# power.net
KiCad netlist of a schematic drawn in EAGLE
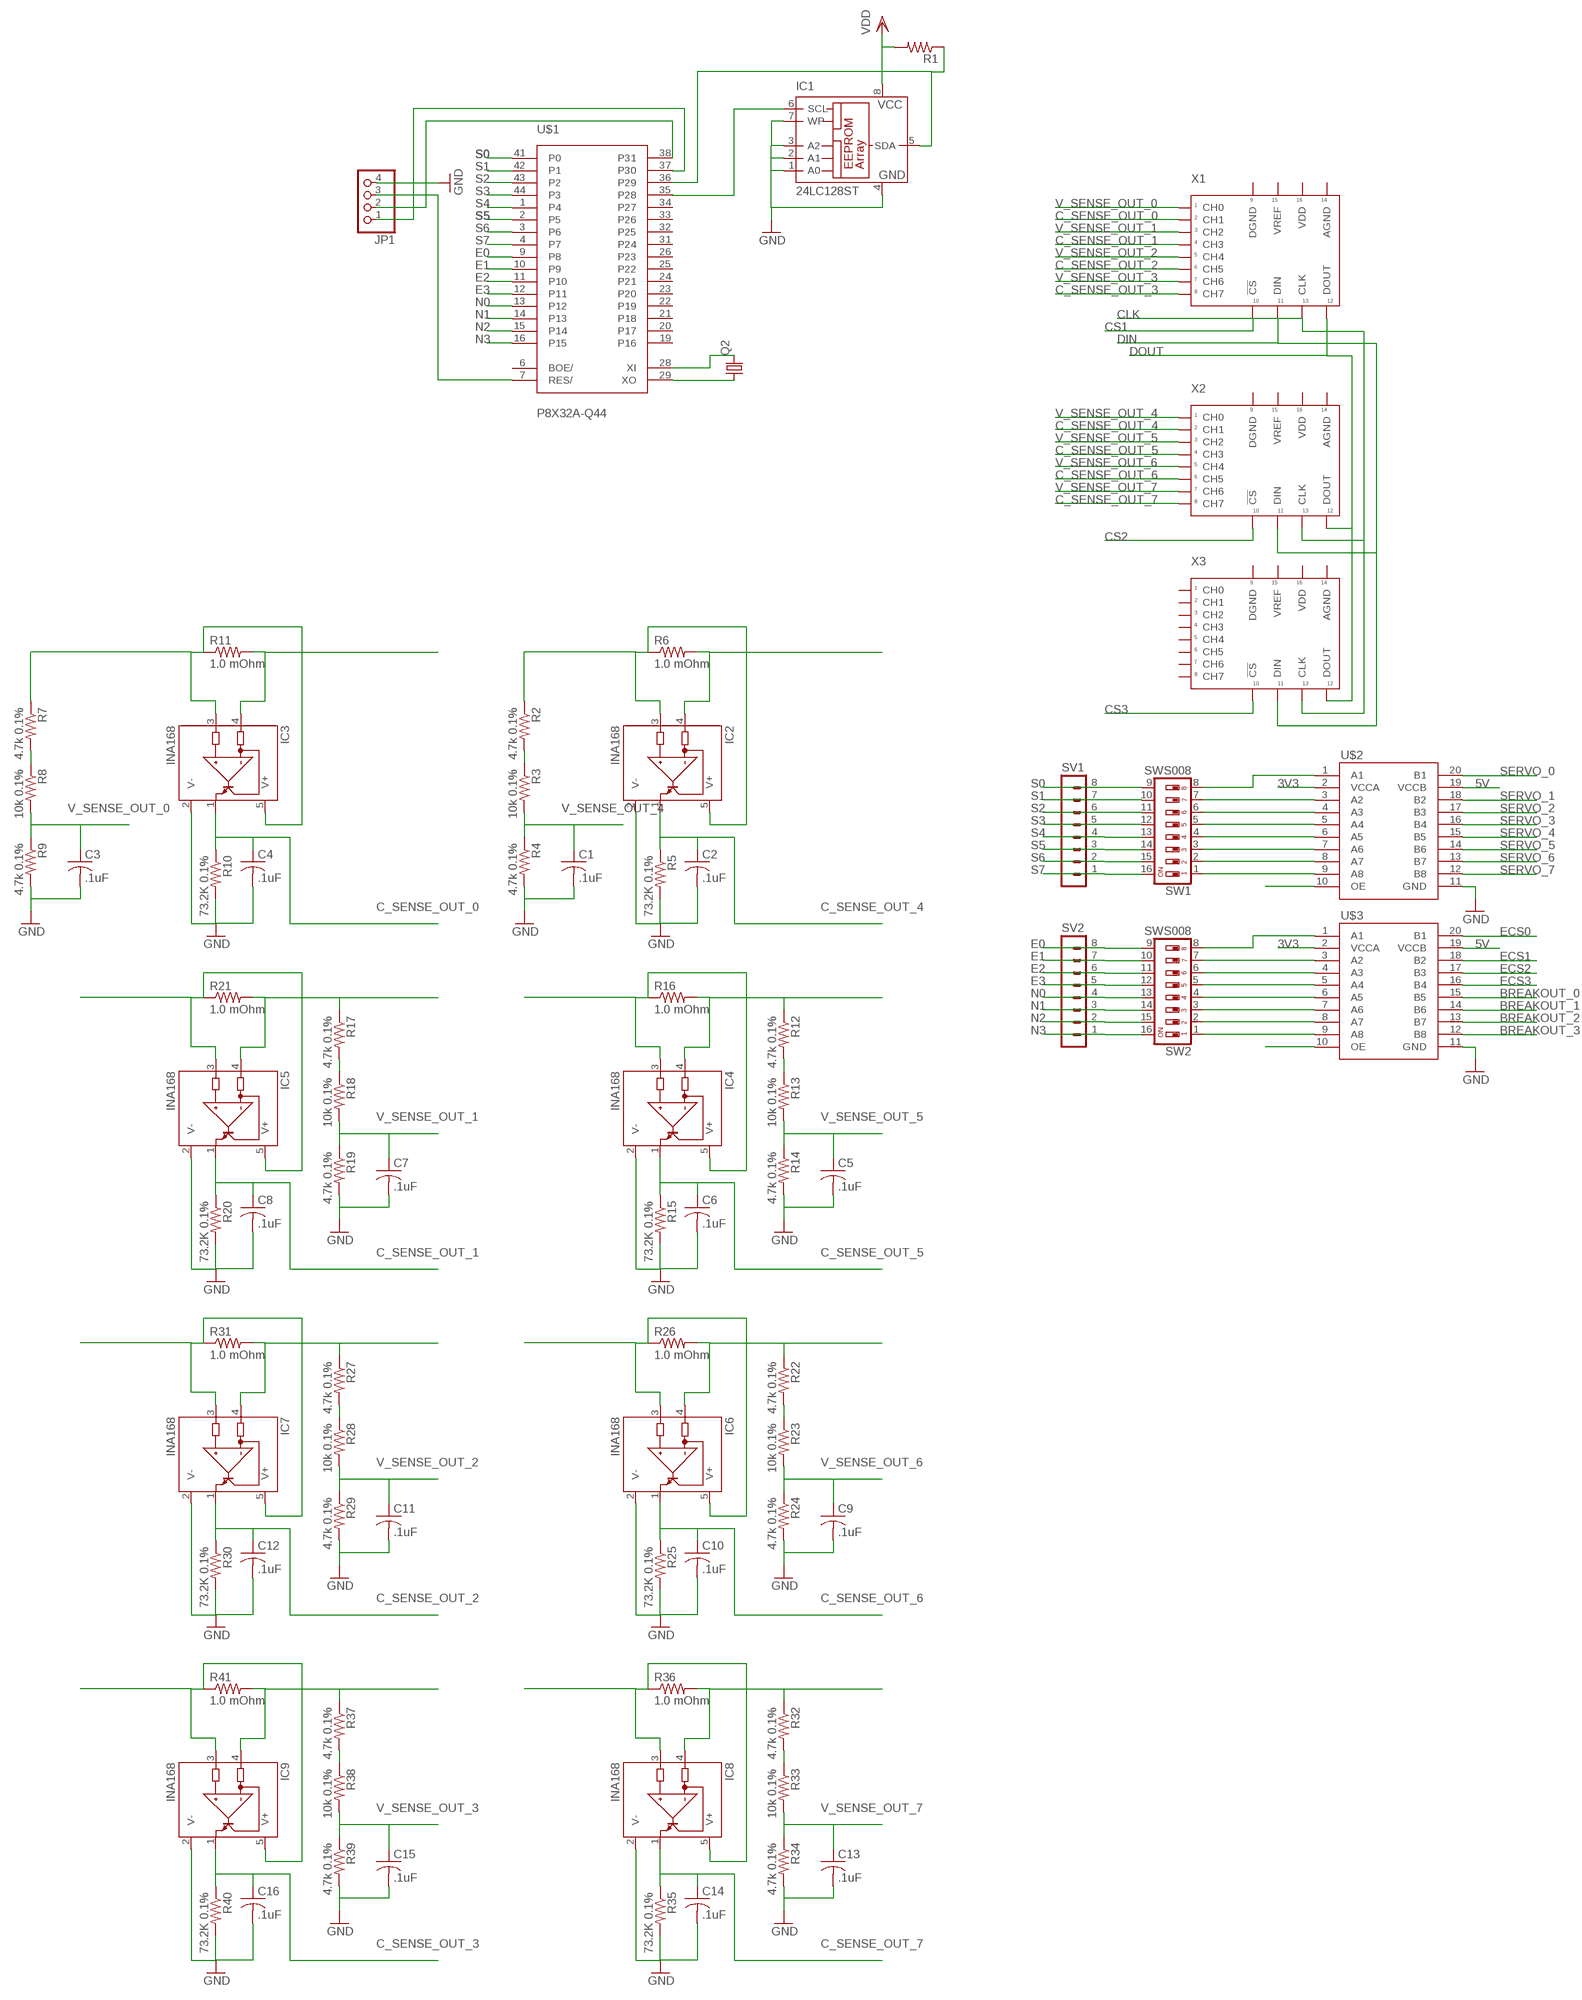
[diagram p0: schematic, sheet 1]

(export (version "E")
  (design (tool "Eeschema 10.0.6"))
  (components
    (comp (ref "C1")
      (value ".1uF")
      (footprint "eagle-import:C0805")
      (libsource (lib "eagle-import") (part "C-USC0805"))
    )
    (comp (ref "C2")
      (value ".1uF")
      (footprint "eagle-import:C0805")
      (libsource (lib "eagle-import") (part "C-USC0805"))
    )
    (comp (ref "C3")
      (value ".1uF")
      (footprint "eagle-import:C0805")
      (libsource (lib "eagle-import") (part "C-USC0805"))
    )
    (comp (ref "C4")
      (value ".1uF")
      (footprint "eagle-import:C0805")
      (libsource (lib "eagle-import") (part "C-USC0805"))
    )
    (comp (ref "C5")
      (value ".1uF")
      (footprint "eagle-import:C0805")
      (libsource (lib "eagle-import") (part "C-USC0805"))
    )
    (comp (ref "C6")
      (value ".1uF")
      (footprint "eagle-import:C0805")
      (libsource (lib "eagle-import") (part "C-USC0805"))
    )
    (comp (ref "C7")
      (value ".1uF")
      (footprint "eagle-import:C0805")
      (libsource (lib "eagle-import") (part "C-USC0805"))
    )
    (comp (ref "C8")
      (value ".1uF")
      (footprint "eagle-import:C0805")
      (libsource (lib "eagle-import") (part "C-USC0805"))
    )
    (comp (ref "C9")
      (value ".1uF")
      (footprint "eagle-import:C0805")
      (libsource (lib "eagle-import") (part "C-USC0805"))
    )
    (comp (ref "C10")
      (value ".1uF")
      (footprint "eagle-import:C0805")
      (libsource (lib "eagle-import") (part "C-USC0805"))
    )
    (comp (ref "C11")
      (value ".1uF")
      (footprint "eagle-import:C0805")
      (libsource (lib "eagle-import") (part "C-USC0805"))
    )
    (comp (ref "C12")
      (value ".1uF")
      (footprint "eagle-import:C0805")
      (libsource (lib "eagle-import") (part "C-USC0805"))
    )
    (comp (ref "C13")
      (value ".1uF")
      (footprint "eagle-import:C0805")
      (libsource (lib "eagle-import") (part "C-USC0805"))
    )
    (comp (ref "C14")
      (value ".1uF")
      (footprint "eagle-import:C0805")
      (libsource (lib "eagle-import") (part "C-USC0805"))
    )
    (comp (ref "C15")
      (value ".1uF")
      (footprint "eagle-import:C0805")
      (libsource (lib "eagle-import") (part "C-USC0805"))
    )
    (comp (ref "C16")
      (value ".1uF")
      (footprint "eagle-import:C0805")
      (libsource (lib "eagle-import") (part "C-USC0805"))
    )
    (comp (ref "IC1")
      (value "24LC128ST")
      (footprint "eagle-import:TSSOP8")
      (fields (field (name "MF") "MICROCHIP") (field (name "MPN") "24LC128-I/ST"))
      (libsource (lib "eagle-import") (part "24STLC128"))
    )
    (comp (ref "IC2")
      (value "INA168")
      (footprint "eagle-import:SOT23-5")
      (fields (field (name "MF") "TEXAS INSTRUMENTS") (field (name "MPN") "INA168NA/250"))
      (libsource (lib "eagle-import") (part "INA168"))
    )
    (comp (ref "IC3")
      (value "INA168")
      (footprint "eagle-import:SOT23-5")
      (fields (field (name "MF") "TEXAS INSTRUMENTS") (field (name "MPN") "INA168NA/250"))
      (libsource (lib "eagle-import") (part "INA168"))
    )
    (comp (ref "IC4")
      (value "INA168")
      (footprint "eagle-import:SOT23-5")
      (fields (field (name "MF") "TEXAS INSTRUMENTS") (field (name "MPN") "INA168NA/250"))
      (libsource (lib "eagle-import") (part "INA168"))
    )
    (comp (ref "IC5")
      (value "INA168")
      (footprint "eagle-import:SOT23-5")
      (fields (field (name "MF") "TEXAS INSTRUMENTS") (field (name "MPN") "INA168NA/250"))
      (libsource (lib "eagle-import") (part "INA168"))
    )
    (comp (ref "IC6")
      (value "INA168")
      (footprint "eagle-import:SOT23-5")
      (fields (field (name "MF") "TEXAS INSTRUMENTS") (field (name "MPN") "INA168NA/250"))
      (libsource (lib "eagle-import") (part "INA168"))
    )
    (comp (ref "IC7")
      (value "INA168")
      (footprint "eagle-import:SOT23-5")
      (fields (field (name "MF") "TEXAS INSTRUMENTS") (field (name "MPN") "INA168NA/250"))
      (libsource (lib "eagle-import") (part "INA168"))
    )
    (comp (ref "IC8")
      (value "INA168")
      (footprint "eagle-import:SOT23-5")
      (fields (field (name "MF") "TEXAS INSTRUMENTS") (field (name "MPN") "INA168NA/250"))
      (libsource (lib "eagle-import") (part "INA168"))
    )
    (comp (ref "IC9")
      (value "INA168")
      (footprint "eagle-import:SOT23-5")
      (fields (field (name "MF") "TEXAS INSTRUMENTS") (field (name "MPN") "INA168NA/250"))
      (libsource (lib "eagle-import") (part "INA168"))
    )
    (comp (ref "JP1")
      (value "PINHD-1X4/90")
      (footprint "eagle-import:1X04_90")
      (libsource (lib "eagle-import") (part "PINHD-1X4/90"))
    )
    (comp (ref "Q2")
      (value "CRYSTALHC49S")
      (footprint "eagle-import:HC49_S")
      (libsource (lib "eagle-import") (part "CRYSTALHC49S"))
    )
    (comp (ref "R1")
      (value "R-US_M0805")
      (footprint "eagle-import:M0805")
      (libsource (lib "eagle-import") (part "R-US_M0805"))
    )
    (comp (ref "R2")
      (value "4.7k 0.1%")
      (footprint "eagle-import:0805")
      (libsource (lib "eagle-import") (part "RESISTOR0805-RES"))
    )
    (comp (ref "R3")
      (value "10k 0.1%")
      (footprint "eagle-import:0805")
      (libsource (lib "eagle-import") (part "RESISTOR0805-RES"))
    )
    (comp (ref "R4")
      (value "4.7k 0.1%")
      (footprint "eagle-import:0805")
      (libsource (lib "eagle-import") (part "RESISTOR0805-RES"))
    )
    (comp (ref "R5")
      (value "73.2K 0.1%")
      (footprint "eagle-import:0805")
      (libsource (lib "eagle-import") (part "RESISTOR0805-RES"))
    )
    (comp (ref "R6")
      (value "1.0 mOhm")
      (footprint "eagle-import:LVK25")
      (libsource (lib "eagle-import") (part "LVK25"))
    )
    (comp (ref "R7")
      (value "4.7k 0.1%")
      (footprint "eagle-import:0805")
      (libsource (lib "eagle-import") (part "RESISTOR0805-RES"))
    )
    (comp (ref "R8")
      (value "10k 0.1%")
      (footprint "eagle-import:0805")
      (libsource (lib "eagle-import") (part "RESISTOR0805-RES"))
    )
    (comp (ref "R9")
      (value "4.7k 0.1%")
      (footprint "eagle-import:0805")
      (libsource (lib "eagle-import") (part "RESISTOR0805-RES"))
    )
    (comp (ref "R10")
      (value "73.2K 0.1%")
      (footprint "eagle-import:0805")
      (libsource (lib "eagle-import") (part "RESISTOR0805-RES"))
    )
    (comp (ref "R11")
      (value "1.0 mOhm")
      (footprint "eagle-import:LVK25")
      (libsource (lib "eagle-import") (part "LVK25"))
    )
    (comp (ref "R12")
      (value "4.7k 0.1%")
      (footprint "eagle-import:0805")
      (libsource (lib "eagle-import") (part "RESISTOR0805-RES"))
    )
    (comp (ref "R13")
      (value "10k 0.1%")
      (footprint "eagle-import:0805")
      (libsource (lib "eagle-import") (part "RESISTOR0805-RES"))
    )
    (comp (ref "R14")
      (value "4.7k 0.1%")
      (footprint "eagle-import:0805")
      (libsource (lib "eagle-import") (part "RESISTOR0805-RES"))
    )
    (comp (ref "R15")
      (value "73.2K 0.1%")
      (footprint "eagle-import:0805")
      (libsource (lib "eagle-import") (part "RESISTOR0805-RES"))
    )
    (comp (ref "R16")
      (value "1.0 mOhm")
      (footprint "eagle-import:LVK25")
      (libsource (lib "eagle-import") (part "LVK25"))
    )
    (comp (ref "R17")
      (value "4.7k 0.1%")
      (footprint "eagle-import:0805")
      (libsource (lib "eagle-import") (part "RESISTOR0805-RES"))
    )
    (comp (ref "R18")
      (value "10k 0.1%")
      (footprint "eagle-import:0805")
      (libsource (lib "eagle-import") (part "RESISTOR0805-RES"))
    )
    (comp (ref "R19")
      (value "4.7k 0.1%")
      (footprint "eagle-import:0805")
      (libsource (lib "eagle-import") (part "RESISTOR0805-RES"))
    )
    (comp (ref "R20")
      (value "73.2K 0.1%")
      (footprint "eagle-import:0805")
      (libsource (lib "eagle-import") (part "RESISTOR0805-RES"))
    )
    (comp (ref "R21")
      (value "1.0 mOhm")
      (footprint "eagle-import:LVK25")
      (libsource (lib "eagle-import") (part "LVK25"))
    )
    (comp (ref "R22")
      (value "4.7k 0.1%")
      (footprint "eagle-import:0805")
      (libsource (lib "eagle-import") (part "RESISTOR0805-RES"))
    )
    (comp (ref "R23")
      (value "10k 0.1%")
      (footprint "eagle-import:0805")
      (libsource (lib "eagle-import") (part "RESISTOR0805-RES"))
    )
    (comp (ref "R24")
      (value "4.7k 0.1%")
      (footprint "eagle-import:0805")
      (libsource (lib "eagle-import") (part "RESISTOR0805-RES"))
    )
    (comp (ref "R25")
      (value "73.2K 0.1%")
      (footprint "eagle-import:0805")
      (libsource (lib "eagle-import") (part "RESISTOR0805-RES"))
    )
    (comp (ref "R26")
      (value "1.0 mOhm")
      (footprint "eagle-import:LVK25")
      (libsource (lib "eagle-import") (part "LVK25"))
    )
    (comp (ref "R27")
      (value "4.7k 0.1%")
      (footprint "eagle-import:0805")
      (libsource (lib "eagle-import") (part "RESISTOR0805-RES"))
    )
    (comp (ref "R28")
      (value "10k 0.1%")
      (footprint "eagle-import:0805")
      (libsource (lib "eagle-import") (part "RESISTOR0805-RES"))
    )
    (comp (ref "R29")
      (value "4.7k 0.1%")
      (footprint "eagle-import:0805")
      (libsource (lib "eagle-import") (part "RESISTOR0805-RES"))
    )
    (comp (ref "R30")
      (value "73.2K 0.1%")
      (footprint "eagle-import:0805")
      (libsource (lib "eagle-import") (part "RESISTOR0805-RES"))
    )
    (comp (ref "R31")
      (value "1.0 mOhm")
      (footprint "eagle-import:LVK25")
      (libsource (lib "eagle-import") (part "LVK25"))
    )
    (comp (ref "R32")
      (value "4.7k 0.1%")
      (footprint "eagle-import:0805")
      (libsource (lib "eagle-import") (part "RESISTOR0805-RES"))
    )
    (comp (ref "R33")
      (value "10k 0.1%")
      (footprint "eagle-import:0805")
      (libsource (lib "eagle-import") (part "RESISTOR0805-RES"))
    )
    (comp (ref "R34")
      (value "4.7k 0.1%")
      (footprint "eagle-import:0805")
      (libsource (lib "eagle-import") (part "RESISTOR0805-RES"))
    )
    (comp (ref "R35")
      (value "73.2K 0.1%")
      (footprint "eagle-import:0805")
      (libsource (lib "eagle-import") (part "RESISTOR0805-RES"))
    )
    (comp (ref "R36")
      (value "1.0 mOhm")
      (footprint "eagle-import:LVK25")
      (libsource (lib "eagle-import") (part "LVK25"))
    )
    (comp (ref "R37")
      (value "4.7k 0.1%")
      (footprint "eagle-import:0805")
      (libsource (lib "eagle-import") (part "RESISTOR0805-RES"))
    )
    (comp (ref "R38")
      (value "10k 0.1%")
      (footprint "eagle-import:0805")
      (libsource (lib "eagle-import") (part "RESISTOR0805-RES"))
    )
    (comp (ref "R39")
      (value "4.7k 0.1%")
      (footprint "eagle-import:0805")
      (libsource (lib "eagle-import") (part "RESISTOR0805-RES"))
    )
    (comp (ref "R40")
      (value "73.2K 0.1%")
      (footprint "eagle-import:0805")
      (libsource (lib "eagle-import") (part "RESISTOR0805-RES"))
    )
    (comp (ref "R41")
      (value "1.0 mOhm")
      (footprint "eagle-import:LVK25")
      (libsource (lib "eagle-import") (part "LVK25"))
    )
    (comp (ref "SV1")
      (value "MA08-1")
      (footprint "eagle-import:MA08-1")
      (libsource (lib "eagle-import") (part "MA08-1"))
    )
    (comp (ref "SV2")
      (value "MA08-1")
      (footprint "eagle-import:MA08-1")
      (libsource (lib "eagle-import") (part "MA08-1"))
    )
    (comp (ref "SW1")
      (value "SWS008")
      (footprint "eagle-import:SMS-008")
      (libsource (lib "eagle-import") (part "SWS008"))
    )
    (comp (ref "SW2")
      (value "SWS008")
      (footprint "eagle-import:SMS-008")
      (libsource (lib "eagle-import") (part "SWS008"))
    )
    (comp (ref "U$1")
      (value "P8X32A-Q44")
      (footprint "eagle-import:P8X32A-Q44")
      (libsource (lib "eagle-import") (part "P8X32A-Q44"))
    )
    (comp (ref "U$2")
      (value "TXB0108PWR")
      (footprint "eagle-import:TSSOP20")
      (libsource (lib "eagle-import") (part "TXB0108PWR"))
    )
    (comp (ref "U$3")
      (value "TXB0108PWR")
      (footprint "eagle-import:TSSOP20")
      (libsource (lib "eagle-import") (part "TXB0108PWR"))
    )
    (comp (ref "X1")
      (value "21298ESMD")
      (footprint "eagle-import:PDIP16")
      (libsource (lib "eagle-import") (part "21298ESMD"))
    )
    (comp (ref "X2")
      (value "21298ESMD")
      (footprint "eagle-import:PDIP16")
      (libsource (lib "eagle-import") (part "21298ESMD"))
    )
    (comp (ref "X3")
      (value "21298ESMD")
      (footprint "eagle-import:PDIP16")
      (libsource (lib "eagle-import") (part "21298ESMD"))
    )
  )
  (nets
    (net (code "1") (name "/3V3") (class "Default")
      (node (ref "U$2") (pin "2") (pinfunction "VCCA_2") (pintype "bidirectional"))
      (node (ref "U$3") (pin "2") (pinfunction "VCCA_2") (pintype "bidirectional"))
    )
    (net (code "2") (name "/5V") (class "Default")
      (node (ref "U$2") (pin "19") (pinfunction "VCCB_19") (pintype "bidirectional"))
      (node (ref "U$3") (pin "19") (pinfunction "VCCB_19") (pintype "bidirectional"))
    )
    (net (code "3") (name "/BREAKOUT_0") (class "Default")
      (node (ref "U$3") (pin "15") (pinfunction "B5_15") (pintype "bidirectional"))
    )
    (net (code "4") (name "/BREAKOUT_1") (class "Default")
      (node (ref "U$3") (pin "14") (pinfunction "B6_14") (pintype "bidirectional"))
    )
    (net (code "5") (name "/BREAKOUT_2") (class "Default")
      (node (ref "U$3") (pin "13") (pinfunction "B7_13") (pintype "bidirectional"))
    )
    (net (code "6") (name "/BREAKOUT_3") (class "Default")
      (node (ref "U$3") (pin "12") (pinfunction "B8_12") (pintype "bidirectional"))
    )
    (net (code "7") (name "/CLK") (class "Default")
      (node (ref "X1") (pin "P$13") (pinfunction "CLK_P$13") (pintype "bidirectional"))
      (node (ref "X2") (pin "P$13") (pinfunction "CLK_P$13") (pintype "bidirectional"))
      (node (ref "X3") (pin "P$13") (pinfunction "CLK_P$13") (pintype "bidirectional"))
    )
    (net (code "8") (name "/CS1") (class "Default")
      (node (ref "X1") (pin "P$10") (pinfunction "~{CS}_P$10") (pintype "bidirectional"))
    )
    (net (code "9") (name "/CS2") (class "Default")
      (node (ref "X2") (pin "P$10") (pinfunction "~{CS}_P$10") (pintype "bidirectional"))
    )
    (net (code "10") (name "/CS3") (class "Default")
      (node (ref "X3") (pin "P$10") (pinfunction "~{CS}_P$10") (pintype "bidirectional"))
    )
    (net (code "11") (name "/C_SENSE_OUT_0") (class "Default")
      (node (ref "C4") (pin "1") (pinfunction "1_1") (pintype "passive"))
      (node (ref "IC3") (pin "1") (pinfunction "OUT_1") (pintype "output"))
      (node (ref "R10") (pin "1") (pinfunction "1_1") (pintype "passive"))
      (node (ref "X1") (pin "P$2") (pinfunction "CH1_P$2") (pintype "bidirectional"))
    )
    (net (code "12") (name "/C_SENSE_OUT_1") (class "Default")
      (node (ref "C8") (pin "1") (pinfunction "1_1") (pintype "passive"))
      (node (ref "IC5") (pin "1") (pinfunction "OUT_1") (pintype "output"))
      (node (ref "R20") (pin "1") (pinfunction "1_1") (pintype "passive"))
      (node (ref "X1") (pin "P$4") (pinfunction "CH3_P$4") (pintype "bidirectional"))
    )
    (net (code "13") (name "/C_SENSE_OUT_2") (class "Default")
      (node (ref "C12") (pin "1") (pinfunction "1_1") (pintype "passive"))
      (node (ref "IC7") (pin "1") (pinfunction "OUT_1") (pintype "output"))
      (node (ref "R30") (pin "1") (pinfunction "1_1") (pintype "passive"))
      (node (ref "X1") (pin "P$6") (pinfunction "CH5_P$6") (pintype "bidirectional"))
    )
    (net (code "14") (name "/C_SENSE_OUT_3") (class "Default")
      (node (ref "C16") (pin "1") (pinfunction "1_1") (pintype "passive"))
      (node (ref "IC9") (pin "1") (pinfunction "OUT_1") (pintype "output"))
      (node (ref "R40") (pin "1") (pinfunction "1_1") (pintype "passive"))
      (node (ref "X1") (pin "P$8") (pinfunction "CH7_P$8") (pintype "bidirectional"))
    )
    (net (code "15") (name "/C_SENSE_OUT_4") (class "Default")
      (node (ref "C2") (pin "1") (pinfunction "1_1") (pintype "passive"))
      (node (ref "IC2") (pin "1") (pinfunction "OUT_1") (pintype "output"))
      (node (ref "R5") (pin "1") (pinfunction "1_1") (pintype "passive"))
      (node (ref "X2") (pin "P$2") (pinfunction "CH1_P$2") (pintype "bidirectional"))
    )
    (net (code "16") (name "/C_SENSE_OUT_5") (class "Default")
      (node (ref "C6") (pin "1") (pinfunction "1_1") (pintype "passive"))
      (node (ref "IC4") (pin "1") (pinfunction "OUT_1") (pintype "output"))
      (node (ref "R15") (pin "1") (pinfunction "1_1") (pintype "passive"))
      (node (ref "X2") (pin "P$4") (pinfunction "CH3_P$4") (pintype "bidirectional"))
    )
    (net (code "17") (name "/C_SENSE_OUT_6") (class "Default")
      (node (ref "C10") (pin "1") (pinfunction "1_1") (pintype "passive"))
      (node (ref "IC6") (pin "1") (pinfunction "OUT_1") (pintype "output"))
      (node (ref "R25") (pin "1") (pinfunction "1_1") (pintype "passive"))
      (node (ref "X2") (pin "P$6") (pinfunction "CH5_P$6") (pintype "bidirectional"))
    )
    (net (code "18") (name "/C_SENSE_OUT_7") (class "Default")
      (node (ref "C14") (pin "1") (pinfunction "1_1") (pintype "passive"))
      (node (ref "IC8") (pin "1") (pinfunction "OUT_1") (pintype "output"))
      (node (ref "R35") (pin "1") (pinfunction "1_1") (pintype "passive"))
      (node (ref "X2") (pin "P$8") (pinfunction "CH7_P$8") (pintype "bidirectional"))
    )
    (net (code "19") (name "/DIN") (class "Default")
      (node (ref "X1") (pin "P$11") (pinfunction "DIN_P$11") (pintype "bidirectional"))
      (node (ref "X2") (pin "P$11") (pinfunction "DIN_P$11") (pintype "bidirectional"))
      (node (ref "X3") (pin "P$11") (pinfunction "DIN_P$11") (pintype "bidirectional"))
    )
    (net (code "20") (name "/DOUT") (class "Default")
      (node (ref "X1") (pin "P$12") (pinfunction "DOUT_P$12") (pintype "bidirectional"))
      (node (ref "X2") (pin "P$12") (pinfunction "DOUT_P$12") (pintype "bidirectional"))
      (node (ref "X3") (pin "P$12") (pinfunction "DOUT_P$12") (pintype "bidirectional"))
    )
    (net (code "21") (name "/E0") (class "Default")
      (node (ref "SV2") (pin "8") (pinfunction "8_8") (pintype "passive"))
      (node (ref "SW2") (pin "9") (pinfunction "9_9") (pintype "passive"))
      (node (ref "U$1") (pin "9") (pinfunction "P8_9") (pintype "bidirectional"))
    )
    (net (code "22") (name "/E1") (class "Default")
      (node (ref "SV2") (pin "7") (pinfunction "7_7") (pintype "passive"))
      (node (ref "SW2") (pin "10") (pinfunction "10_10") (pintype "passive"))
      (node (ref "U$1") (pin "10") (pinfunction "P9_10") (pintype "bidirectional"))
    )
    (net (code "23") (name "/E2") (class "Default")
      (node (ref "SV2") (pin "6") (pinfunction "6_6") (pintype "passive"))
      (node (ref "SW2") (pin "11") (pinfunction "11_11") (pintype "passive"))
      (node (ref "U$1") (pin "11") (pinfunction "P10_11") (pintype "bidirectional"))
    )
    (net (code "24") (name "/E3") (class "Default")
      (node (ref "SV2") (pin "5") (pinfunction "5_5") (pintype "passive"))
      (node (ref "SW2") (pin "12") (pinfunction "12_12") (pintype "passive"))
      (node (ref "U$1") (pin "12") (pinfunction "P11_12") (pintype "bidirectional"))
    )
    (net (code "25") (name "/ECS0") (class "Default")
      (node (ref "U$3") (pin "20") (pinfunction "B1_20") (pintype "bidirectional"))
    )
    (net (code "26") (name "/ECS1") (class "Default")
      (node (ref "U$3") (pin "18") (pinfunction "B2_18") (pintype "bidirectional"))
    )
    (net (code "27") (name "/ECS2") (class "Default")
      (node (ref "U$3") (pin "17") (pinfunction "B3_17") (pintype "bidirectional"))
    )
    (net (code "28") (name "/ECS3") (class "Default")
      (node (ref "U$3") (pin "16") (pinfunction "B4_16") (pintype "bidirectional"))
    )
    (net (code "29") (name "/N0") (class "Default")
      (node (ref "SV2") (pin "4") (pinfunction "4_4") (pintype "passive"))
      (node (ref "SW2") (pin "13") (pinfunction "13_13") (pintype "passive"))
      (node (ref "U$1") (pin "13") (pinfunction "P12_13") (pintype "bidirectional"))
    )
    (net (code "30") (name "/N1") (class "Default")
      (node (ref "SV2") (pin "3") (pinfunction "3_3") (pintype "passive"))
      (node (ref "SW2") (pin "14") (pinfunction "14_14") (pintype "passive"))
      (node (ref "U$1") (pin "14") (pinfunction "P13_14") (pintype "bidirectional"))
    )
    (net (code "31") (name "/N2") (class "Default")
      (node (ref "SV2") (pin "2") (pinfunction "2_2") (pintype "passive"))
      (node (ref "SW2") (pin "15") (pinfunction "15_15") (pintype "passive"))
      (node (ref "U$1") (pin "15") (pinfunction "P14_15") (pintype "bidirectional"))
    )
    (net (code "32") (name "/N3") (class "Default")
      (node (ref "SV2") (pin "1") (pinfunction "1_1") (pintype "passive"))
      (node (ref "SW2") (pin "16") (pinfunction "16_16") (pintype "passive"))
      (node (ref "U$1") (pin "16") (pinfunction "P15_16") (pintype "bidirectional"))
    )
    (net (code "33") (name "/S0") (class "Default")
      (node (ref "SV1") (pin "8") (pinfunction "8_8") (pintype "passive"))
      (node (ref "SW1") (pin "9") (pinfunction "9_9") (pintype "passive"))
      (node (ref "U$1") (pin "41") (pinfunction "P0_41") (pintype "bidirectional"))
    )
    (net (code "34") (name "/S1") (class "Default")
      (node (ref "SV1") (pin "7") (pinfunction "7_7") (pintype "passive"))
      (node (ref "SW1") (pin "10") (pinfunction "10_10") (pintype "passive"))
      (node (ref "U$1") (pin "42") (pinfunction "P1_42") (pintype "bidirectional"))
    )
    (net (code "35") (name "/S2") (class "Default")
      (node (ref "SV1") (pin "6") (pinfunction "6_6") (pintype "passive"))
      (node (ref "SW1") (pin "11") (pinfunction "11_11") (pintype "passive"))
      (node (ref "U$1") (pin "43") (pinfunction "P2_43") (pintype "bidirectional"))
    )
    (net (code "36") (name "/S3") (class "Default")
      (node (ref "SV1") (pin "5") (pinfunction "5_5") (pintype "passive"))
      (node (ref "SW1") (pin "12") (pinfunction "12_12") (pintype "passive"))
      (node (ref "U$1") (pin "44") (pinfunction "P3_44") (pintype "bidirectional"))
    )
    (net (code "37") (name "/S4") (class "Default")
      (node (ref "SV1") (pin "4") (pinfunction "4_4") (pintype "passive"))
      (node (ref "SW1") (pin "13") (pinfunction "13_13") (pintype "passive"))
      (node (ref "U$1") (pin "1") (pinfunction "P4_1") (pintype "bidirectional"))
    )
    (net (code "38") (name "/S5") (class "Default")
      (node (ref "SV1") (pin "3") (pinfunction "3_3") (pintype "passive"))
      (node (ref "SW1") (pin "14") (pinfunction "14_14") (pintype "passive"))
      (node (ref "U$1") (pin "2") (pinfunction "P5_2") (pintype "bidirectional"))
    )
    (net (code "39") (name "/S6") (class "Default")
      (node (ref "SV1") (pin "2") (pinfunction "2_2") (pintype "passive"))
      (node (ref "SW1") (pin "15") (pinfunction "15_15") (pintype "passive"))
      (node (ref "U$1") (pin "3") (pinfunction "P6_3") (pintype "bidirectional"))
    )
    (net (code "40") (name "/S7") (class "Default")
      (node (ref "SV1") (pin "1") (pinfunction "1_1") (pintype "passive"))
      (node (ref "SW1") (pin "16") (pinfunction "16_16") (pintype "passive"))
      (node (ref "U$1") (pin "4") (pinfunction "P7_4") (pintype "bidirectional"))
    )
    (net (code "41") (name "/SERVO_0") (class "Default")
      (node (ref "U$2") (pin "20") (pinfunction "B1_20") (pintype "bidirectional"))
    )
    (net (code "42") (name "/SERVO_1") (class "Default")
      (node (ref "U$2") (pin "18") (pinfunction "B2_18") (pintype "bidirectional"))
    )
    (net (code "43") (name "/SERVO_2") (class "Default")
      (node (ref "U$2") (pin "17") (pinfunction "B3_17") (pintype "bidirectional"))
    )
    (net (code "44") (name "/SERVO_3") (class "Default")
      (node (ref "U$2") (pin "16") (pinfunction "B4_16") (pintype "bidirectional"))
    )
    (net (code "45") (name "/SERVO_4") (class "Default")
      (node (ref "U$2") (pin "15") (pinfunction "B5_15") (pintype "bidirectional"))
    )
    (net (code "46") (name "/SERVO_5") (class "Default")
      (node (ref "U$2") (pin "14") (pinfunction "B6_14") (pintype "bidirectional"))
    )
    (net (code "47") (name "/SERVO_6") (class "Default")
      (node (ref "U$2") (pin "13") (pinfunction "B7_13") (pintype "bidirectional"))
    )
    (net (code "48") (name "/SERVO_7") (class "Default")
      (node (ref "U$2") (pin "12") (pinfunction "B8_12") (pintype "bidirectional"))
    )
    (net (code "49") (name "/V_SENSE_OUT_0") (class "Default")
      (node (ref "C3") (pin "1") (pinfunction "1_1") (pintype "passive"))
      (node (ref "R8") (pin "2") (pinfunction "2_2") (pintype "passive"))
      (node (ref "R9") (pin "1") (pinfunction "1_1") (pintype "passive"))
      (node (ref "X1") (pin "P$1") (pinfunction "CH0_P$1") (pintype "bidirectional"))
    )
    (net (code "50") (name "/V_SENSE_OUT_1") (class "Default")
      (node (ref "C7") (pin "1") (pinfunction "1_1") (pintype "passive"))
      (node (ref "R18") (pin "2") (pinfunction "2_2") (pintype "passive"))
      (node (ref "R19") (pin "1") (pinfunction "1_1") (pintype "passive"))
      (node (ref "X1") (pin "P$3") (pinfunction "CH2_P$3") (pintype "bidirectional"))
    )
    (net (code "51") (name "/V_SENSE_OUT_2") (class "Default")
      (node (ref "C11") (pin "1") (pinfunction "1_1") (pintype "passive"))
      (node (ref "R28") (pin "2") (pinfunction "2_2") (pintype "passive"))
      (node (ref "R29") (pin "1") (pinfunction "1_1") (pintype "passive"))
      (node (ref "X1") (pin "P$5") (pinfunction "CH4_P$5") (pintype "bidirectional"))
    )
    (net (code "52") (name "/V_SENSE_OUT_3") (class "Default")
      (node (ref "C15") (pin "1") (pinfunction "1_1") (pintype "passive"))
      (node (ref "R38") (pin "2") (pinfunction "2_2") (pintype "passive"))
      (node (ref "R39") (pin "1") (pinfunction "1_1") (pintype "passive"))
      (node (ref "X1") (pin "P$7") (pinfunction "CH6_P$7") (pintype "bidirectional"))
    )
    (net (code "53") (name "/V_SENSE_OUT_4") (class "Default")
      (node (ref "C1") (pin "1") (pinfunction "1_1") (pintype "passive"))
      (node (ref "R3") (pin "2") (pinfunction "2_2") (pintype "passive"))
      (node (ref "R4") (pin "1") (pinfunction "1_1") (pintype "passive"))
      (node (ref "X2") (pin "P$1") (pinfunction "CH0_P$1") (pintype "bidirectional"))
    )
    (net (code "54") (name "/V_SENSE_OUT_5") (class "Default")
      (node (ref "C5") (pin "1") (pinfunction "1_1") (pintype "passive"))
      (node (ref "R13") (pin "2") (pinfunction "2_2") (pintype "passive"))
      (node (ref "R14") (pin "1") (pinfunction "1_1") (pintype "passive"))
      (node (ref "X2") (pin "P$3") (pinfunction "CH2_P$3") (pintype "bidirectional"))
    )
    (net (code "55") (name "/V_SENSE_OUT_6") (class "Default")
      (node (ref "C9") (pin "1") (pinfunction "1_1") (pintype "passive"))
      (node (ref "R23") (pin "2") (pinfunction "2_2") (pintype "passive"))
      (node (ref "R24") (pin "1") (pinfunction "1_1") (pintype "passive"))
      (node (ref "X2") (pin "P$5") (pinfunction "CH4_P$5") (pintype "bidirectional"))
    )
    (net (code "56") (name "/V_SENSE_OUT_7") (class "Default")
      (node (ref "C13") (pin "1") (pinfunction "1_1") (pintype "passive"))
      (node (ref "R33") (pin "2") (pinfunction "2_2") (pintype "passive"))
      (node (ref "R34") (pin "1") (pinfunction "1_1") (pintype "passive"))
      (node (ref "X2") (pin "P$7") (pinfunction "CH6_P$7") (pintype "bidirectional"))
    )
    (net (code "57") (name "GND") (class "Default")
      (node (ref "C1") (pin "2") (pinfunction "2_2") (pintype "passive"))
      (node (ref "C10") (pin "2") (pinfunction "2_2") (pintype "passive"))
      (node (ref "C11") (pin "2") (pinfunction "2_2") (pintype "passive"))
      (node (ref "C12") (pin "2") (pinfunction "2_2") (pintype "passive"))
      (node (ref "C13") (pin "2") (pinfunction "2_2") (pintype "passive"))
      (node (ref "C14") (pin "2") (pinfunction "2_2") (pintype "passive"))
      (node (ref "C15") (pin "2") (pinfunction "2_2") (pintype "passive"))
      (node (ref "C16") (pin "2") (pinfunction "2_2") (pintype "passive"))
      (node (ref "C2") (pin "2") (pinfunction "2_2") (pintype "passive"))
      (node (ref "C3") (pin "2") (pinfunction "2_2") (pintype "passive"))
      (node (ref "C4") (pin "2") (pinfunction "2_2") (pintype "passive"))
      (node (ref "C5") (pin "2") (pinfunction "2_2") (pintype "passive"))
      (node (ref "C6") (pin "2") (pinfunction "2_2") (pintype "passive"))
      (node (ref "C7") (pin "2") (pinfunction "2_2") (pintype "passive"))
      (node (ref "C8") (pin "2") (pinfunction "2_2") (pintype "passive"))
      (node (ref "C9") (pin "2") (pinfunction "2_2") (pintype "passive"))
      (node (ref "IC1") (pin "1") (pinfunction "A0_1") (pintype "input"))
      (node (ref "IC1") (pin "2") (pinfunction "A1_2") (pintype "input"))
      (node (ref "IC1") (pin "3") (pinfunction "A2_3") (pintype "input"))
      (node (ref "IC1") (pin "4") (pinfunction "GND_4") (pintype "power_in"))
      (node (ref "IC1") (pin "7") (pinfunction "WP_7") (pintype "input"))
      (node (ref "IC2") (pin "2") (pinfunction "V-_2") (pintype "power_in"))
      (node (ref "IC3") (pin "2") (pinfunction "V-_2") (pintype "power_in"))
      (node (ref "IC4") (pin "2") (pinfunction "V-_2") (pintype "power_in"))
      (node (ref "IC5") (pin "2") (pinfunction "V-_2") (pintype "power_in"))
      (node (ref "IC6") (pin "2") (pinfunction "V-_2") (pintype "power_in"))
      (node (ref "IC7") (pin "2") (pinfunction "V-_2") (pintype "power_in"))
      (node (ref "IC8") (pin "2") (pinfunction "V-_2") (pintype "power_in"))
      (node (ref "IC9") (pin "2") (pinfunction "V-_2") (pintype "power_in"))
      (node (ref "JP1") (pin "4") (pinfunction "4_4") (pintype "passive"))
      (node (ref "R10") (pin "2") (pinfunction "2_2") (pintype "passive"))
      (node (ref "R14") (pin "2") (pinfunction "2_2") (pintype "passive"))
      (node (ref "R15") (pin "2") (pinfunction "2_2") (pintype "passive"))
      (node (ref "R19") (pin "2") (pinfunction "2_2") (pintype "passive"))
      (node (ref "R20") (pin "2") (pinfunction "2_2") (pintype "passive"))
      (node (ref "R24") (pin "2") (pinfunction "2_2") (pintype "passive"))
      (node (ref "R25") (pin "2") (pinfunction "2_2") (pintype "passive"))
      (node (ref "R29") (pin "2") (pinfunction "2_2") (pintype "passive"))
      (node (ref "R30") (pin "2") (pinfunction "2_2") (pintype "passive"))
      (node (ref "R34") (pin "2") (pinfunction "2_2") (pintype "passive"))
      (node (ref "R35") (pin "2") (pinfunction "2_2") (pintype "passive"))
      (node (ref "R39") (pin "2") (pinfunction "2_2") (pintype "passive"))
      (node (ref "R4") (pin "2") (pinfunction "2_2") (pintype "passive"))
      (node (ref "R40") (pin "2") (pinfunction "2_2") (pintype "passive"))
      (node (ref "R5") (pin "2") (pinfunction "2_2") (pintype "passive"))
      (node (ref "R9") (pin "2") (pinfunction "2_2") (pintype "passive"))
      (node (ref "U$2") (pin "11") (pinfunction "GND_11") (pintype "bidirectional"))
      (node (ref "U$3") (pin "11") (pinfunction "GND_11") (pintype "bidirectional"))
    )
    (net (code "58") (name "Net-(IC1-SCL)") (class "Default")
      (node (ref "IC1") (pin "6") (pinfunction "SCL_6") (pintype "input"))
      (node (ref "U$1") (pin "35") (pinfunction "P28_35") (pintype "bidirectional"))
    )
    (net (code "59") (name "Net-(IC1-SDA)") (class "Default")
      (node (ref "IC1") (pin "5") (pinfunction "SDA_5") (pintype "bidirectional"))
      (node (ref "R1") (pin "1") (pinfunction "1_1") (pintype "passive"))
      (node (ref "U$1") (pin "36") (pinfunction "P29_36") (pintype "bidirectional"))
    )
    (net (code "60") (name "Net-(IC2-IN+)") (class "Default")
      (node (ref "IC2") (pin "3") (pinfunction "IN+_3") (pintype "input"))
      (node (ref "IC2") (pin "5") (pinfunction "V+_5") (pintype "power_in"))
      (node (ref "R2") (pin "1") (pinfunction "1_1") (pintype "passive"))
      (node (ref "R6") (pin "P$1") (pinfunction "1_P$1") (pintype "passive"))
    )
    (net (code "61") (name "Net-(IC2-IN-)") (class "Default")
      (node (ref "IC2") (pin "4") (pinfunction "IN-_4") (pintype "input"))
      (node (ref "R6") (pin "P$5") (pinfunction "2_P$5") (pintype "passive"))
    )
    (net (code "62") (name "Net-(IC3-IN+)") (class "Default")
      (node (ref "IC3") (pin "3") (pinfunction "IN+_3") (pintype "input"))
      (node (ref "IC3") (pin "5") (pinfunction "V+_5") (pintype "power_in"))
      (node (ref "R11") (pin "P$1") (pinfunction "1_P$1") (pintype "passive"))
      (node (ref "R7") (pin "1") (pinfunction "1_1") (pintype "passive"))
    )
    (net (code "63") (name "Net-(IC3-IN-)") (class "Default")
      (node (ref "IC3") (pin "4") (pinfunction "IN-_4") (pintype "input"))
      (node (ref "R11") (pin "P$5") (pinfunction "2_P$5") (pintype "passive"))
    )
    (net (code "64") (name "Net-(IC4-IN+)") (class "Default")
      (node (ref "IC4") (pin "3") (pinfunction "IN+_3") (pintype "input"))
      (node (ref "IC4") (pin "5") (pinfunction "V+_5") (pintype "power_in"))
      (node (ref "R16") (pin "P$1") (pinfunction "1_P$1") (pintype "passive"))
    )
    (net (code "65") (name "Net-(IC4-IN-)") (class "Default")
      (node (ref "IC4") (pin "4") (pinfunction "IN-_4") (pintype "input"))
      (node (ref "R12") (pin "1") (pinfunction "1_1") (pintype "passive"))
      (node (ref "R16") (pin "P$5") (pinfunction "2_P$5") (pintype "passive"))
    )
    (net (code "66") (name "Net-(IC5-IN+)") (class "Default")
      (node (ref "IC5") (pin "3") (pinfunction "IN+_3") (pintype "input"))
      (node (ref "IC5") (pin "5") (pinfunction "V+_5") (pintype "power_in"))
      (node (ref "R21") (pin "P$1") (pinfunction "1_P$1") (pintype "passive"))
    )
    (net (code "67") (name "Net-(IC5-IN-)") (class "Default")
      (node (ref "IC5") (pin "4") (pinfunction "IN-_4") (pintype "input"))
      (node (ref "R17") (pin "1") (pinfunction "1_1") (pintype "passive"))
      (node (ref "R21") (pin "P$5") (pinfunction "2_P$5") (pintype "passive"))
    )
    (net (code "68") (name "Net-(IC6-IN+)") (class "Default")
      (node (ref "IC6") (pin "3") (pinfunction "IN+_3") (pintype "input"))
      (node (ref "IC6") (pin "5") (pinfunction "V+_5") (pintype "power_in"))
      (node (ref "R26") (pin "P$1") (pinfunction "1_P$1") (pintype "passive"))
    )
    (net (code "69") (name "Net-(IC6-IN-)") (class "Default")
      (node (ref "IC6") (pin "4") (pinfunction "IN-_4") (pintype "input"))
      (node (ref "R22") (pin "1") (pinfunction "1_1") (pintype "passive"))
      (node (ref "R26") (pin "P$5") (pinfunction "2_P$5") (pintype "passive"))
    )
    (net (code "70") (name "Net-(IC7-IN+)") (class "Default")
      (node (ref "IC7") (pin "3") (pinfunction "IN+_3") (pintype "input"))
      (node (ref "IC7") (pin "5") (pinfunction "V+_5") (pintype "power_in"))
      (node (ref "R31") (pin "P$1") (pinfunction "1_P$1") (pintype "passive"))
    )
    (net (code "71") (name "Net-(IC7-IN-)") (class "Default")
      (node (ref "IC7") (pin "4") (pinfunction "IN-_4") (pintype "input"))
      (node (ref "R27") (pin "1") (pinfunction "1_1") (pintype "passive"))
      (node (ref "R31") (pin "P$5") (pinfunction "2_P$5") (pintype "passive"))
    )
    (net (code "72") (name "Net-(IC8-IN+)") (class "Default")
      (node (ref "IC8") (pin "3") (pinfunction "IN+_3") (pintype "input"))
      (node (ref "IC8") (pin "5") (pinfunction "V+_5") (pintype "power_in"))
      (node (ref "R36") (pin "P$1") (pinfunction "1_P$1") (pintype "passive"))
    )
    (net (code "73") (name "Net-(IC8-IN-)") (class "Default")
      (node (ref "IC8") (pin "4") (pinfunction "IN-_4") (pintype "input"))
      (node (ref "R32") (pin "1") (pinfunction "1_1") (pintype "passive"))
      (node (ref "R36") (pin "P$5") (pinfunction "2_P$5") (pintype "passive"))
    )
    (net (code "74") (name "Net-(IC9-IN+)") (class "Default")
      (node (ref "IC9") (pin "3") (pinfunction "IN+_3") (pintype "input"))
      (node (ref "IC9") (pin "5") (pinfunction "V+_5") (pintype "power_in"))
      (node (ref "R41") (pin "P$1") (pinfunction "1_P$1") (pintype "passive"))
    )
    (net (code "75") (name "Net-(IC9-IN-)") (class "Default")
      (node (ref "IC9") (pin "4") (pinfunction "IN-_4") (pintype "input"))
      (node (ref "R37") (pin "1") (pinfunction "1_1") (pintype "passive"))
      (node (ref "R41") (pin "P$5") (pinfunction "2_P$5") (pintype "passive"))
    )
    (net (code "76") (name "Net-(R2-Pad2)") (class "Default")
      (node (ref "R2") (pin "2") (pinfunction "2_2") (pintype "passive"))
      (node (ref "R3") (pin "1") (pinfunction "1_1") (pintype "passive"))
    )
    (net (code "77") (name "Net-(R7-Pad2)") (class "Default")
      (node (ref "R7") (pin "2") (pinfunction "2_2") (pintype "passive"))
      (node (ref "R8") (pin "1") (pinfunction "1_1") (pintype "passive"))
    )
    (net (code "78") (name "Net-(R12-Pad2)") (class "Default")
      (node (ref "R12") (pin "2") (pinfunction "2_2") (pintype "passive"))
      (node (ref "R13") (pin "1") (pinfunction "1_1") (pintype "passive"))
    )
    (net (code "79") (name "Net-(R17-Pad2)") (class "Default")
      (node (ref "R17") (pin "2") (pinfunction "2_2") (pintype "passive"))
      (node (ref "R18") (pin "1") (pinfunction "1_1") (pintype "passive"))
    )
    (net (code "80") (name "Net-(R22-Pad2)") (class "Default")
      (node (ref "R22") (pin "2") (pinfunction "2_2") (pintype "passive"))
      (node (ref "R23") (pin "1") (pinfunction "1_1") (pintype "passive"))
    )
    (net (code "81") (name "Net-(R27-Pad2)") (class "Default")
      (node (ref "R27") (pin "2") (pinfunction "2_2") (pintype "passive"))
      (node (ref "R28") (pin "1") (pinfunction "1_1") (pintype "passive"))
    )
    (net (code "82") (name "Net-(R32-Pad2)") (class "Default")
      (node (ref "R32") (pin "2") (pinfunction "2_2") (pintype "passive"))
      (node (ref "R33") (pin "1") (pinfunction "1_1") (pintype "passive"))
    )
    (net (code "83") (name "Net-(R37-Pad2)") (class "Default")
      (node (ref "R37") (pin "2") (pinfunction "2_2") (pintype "passive"))
      (node (ref "R38") (pin "1") (pinfunction "1_1") (pintype "passive"))
    )
    (net (code "84") (name "Net-(U$1B-P30)") (class "Default")
      (node (ref "JP1") (pin "1") (pinfunction "1_1") (pintype "passive"))
      (node (ref "U$1") (pin "37") (pinfunction "P30_37") (pintype "bidirectional"))
    )
    (net (code "85") (name "Net-(U$1B-P31)") (class "Default")
      (node (ref "JP1") (pin "2") (pinfunction "2_2") (pintype "passive"))
      (node (ref "U$1") (pin "38") (pinfunction "P31_38") (pintype "bidirectional"))
    )
    (net (code "86") (name "Net-(U$1B-RES{slash})") (class "Default")
      (node (ref "JP1") (pin "3") (pinfunction "3_3") (pintype "passive"))
      (node (ref "U$1") (pin "7") (pinfunction "RES/_7") (pintype "bidirectional"))
    )
    (net (code "87") (name "Net-(U$1B-XI)") (class "Default")
      (node (ref "Q2") (pin "2") (pinfunction "2_2") (pintype "passive"))
      (node (ref "U$1") (pin "28") (pinfunction "XI_28") (pintype "input"))
    )
    (net (code "88") (name "Net-(U$1B-XO)") (class "Default")
      (node (ref "Q2") (pin "1") (pinfunction "1_1") (pintype "passive"))
      (node (ref "U$1") (pin "29") (pinfunction "XO_29") (pintype "output"))
    )
    (net (code "89") (name "Net-(U$2-A1)") (class "Default")
      (node (ref "SW1") (pin "8") (pinfunction "8_8") (pintype "passive"))
      (node (ref "U$2") (pin "1") (pinfunction "A1_1") (pintype "bidirectional"))
    )
    (net (code "90") (name "Net-(U$2-A2)") (class "Default")
      (node (ref "SW1") (pin "7") (pinfunction "7_7") (pintype "passive"))
      (node (ref "U$2") (pin "3") (pinfunction "A2_3") (pintype "bidirectional"))
    )
    (net (code "91") (name "Net-(U$2-A3)") (class "Default")
      (node (ref "SW1") (pin "6") (pinfunction "6_6") (pintype "passive"))
      (node (ref "U$2") (pin "4") (pinfunction "A3_4") (pintype "bidirectional"))
    )
    (net (code "92") (name "Net-(U$2-A4)") (class "Default")
      (node (ref "SW1") (pin "5") (pinfunction "5_5") (pintype "passive"))
      (node (ref "U$2") (pin "5") (pinfunction "A4_5") (pintype "bidirectional"))
    )
    (net (code "93") (name "Net-(U$2-A5)") (class "Default")
      (node (ref "SW1") (pin "4") (pinfunction "4_4") (pintype "passive"))
      (node (ref "U$2") (pin "6") (pinfunction "A5_6") (pintype "bidirectional"))
    )
    (net (code "94") (name "Net-(U$2-A6)") (class "Default")
      (node (ref "SW1") (pin "3") (pinfunction "3_3") (pintype "passive"))
      (node (ref "U$2") (pin "7") (pinfunction "A6_7") (pintype "bidirectional"))
    )
    (net (code "95") (name "Net-(U$2-A7)") (class "Default")
      (node (ref "SW1") (pin "2") (pinfunction "2_2") (pintype "passive"))
      (node (ref "U$2") (pin "8") (pinfunction "A7_8") (pintype "bidirectional"))
    )
    (net (code "96") (name "Net-(U$2-A8)") (class "Default")
      (node (ref "SW1") (pin "1") (pinfunction "1_1") (pintype "passive"))
      (node (ref "U$2") (pin "9") (pinfunction "A8_9") (pintype "bidirectional"))
    )
    (net (code "97") (name "Net-(U$3-A1)") (class "Default")
      (node (ref "SW2") (pin "8") (pinfunction "8_8") (pintype "passive"))
      (node (ref "U$3") (pin "1") (pinfunction "A1_1") (pintype "bidirectional"))
    )
    (net (code "98") (name "Net-(U$3-A2)") (class "Default")
      (node (ref "SW2") (pin "7") (pinfunction "7_7") (pintype "passive"))
      (node (ref "U$3") (pin "3") (pinfunction "A2_3") (pintype "bidirectional"))
    )
    (net (code "99") (name "Net-(U$3-A3)") (class "Default")
      (node (ref "SW2") (pin "6") (pinfunction "6_6") (pintype "passive"))
      (node (ref "U$3") (pin "4") (pinfunction "A3_4") (pintype "bidirectional"))
    )
    (net (code "100") (name "Net-(U$3-A4)") (class "Default")
      (node (ref "SW2") (pin "5") (pinfunction "5_5") (pintype "passive"))
      (node (ref "U$3") (pin "5") (pinfunction "A4_5") (pintype "bidirectional"))
    )
    (net (code "101") (name "Net-(U$3-A5)") (class "Default")
      (node (ref "SW2") (pin "4") (pinfunction "4_4") (pintype "passive"))
      (node (ref "U$3") (pin "6") (pinfunction "A5_6") (pintype "bidirectional"))
    )
    (net (code "102") (name "Net-(U$3-A6)") (class "Default")
      (node (ref "SW2") (pin "3") (pinfunction "3_3") (pintype "passive"))
      (node (ref "U$3") (pin "7") (pinfunction "A6_7") (pintype "bidirectional"))
    )
    (net (code "103") (name "Net-(U$3-A7)") (class "Default")
      (node (ref "SW2") (pin "2") (pinfunction "2_2") (pintype "passive"))
      (node (ref "U$3") (pin "8") (pinfunction "A7_8") (pintype "bidirectional"))
    )
    (net (code "104") (name "Net-(U$3-A8)") (class "Default")
      (node (ref "SW2") (pin "1") (pinfunction "1_1") (pintype "passive"))
      (node (ref "U$3") (pin "9") (pinfunction "A8_9") (pintype "bidirectional"))
    )
    (net (code "105") (name "VDD") (class "Default")
      (node (ref "IC1") (pin "8") (pinfunction "VCC_8") (pintype "power_in"))
      (node (ref "R1") (pin "2") (pinfunction "2_2") (pintype "passive"))
    )
    (net (code "106") (name "unconnected-(U$1B-BOE{slash}-Pad6)") (class "Default")
      (node (ref "U$1") (pin "6") (pinfunction "BOE/_6") (pintype "input"))
    )
    (net (code "107") (name "unconnected-(U$1B-P16-Pad19)") (class "Default")
      (node (ref "U$1") (pin "19") (pinfunction "P16_19") (pintype "bidirectional"))
    )
    (net (code "108") (name "unconnected-(U$1B-P17-Pad20)") (class "Default")
      (node (ref "U$1") (pin "20") (pinfunction "P17_20") (pintype "bidirectional"))
    )
    (net (code "109") (name "unconnected-(U$1B-P18-Pad21)") (class "Default")
      (node (ref "U$1") (pin "21") (pinfunction "P18_21") (pintype "bidirectional"))
    )
    (net (code "110") (name "unconnected-(U$1B-P19-Pad22)") (class "Default")
      (node (ref "U$1") (pin "22") (pinfunction "P19_22") (pintype "bidirectional"))
    )
    (net (code "111") (name "unconnected-(U$1B-P20-Pad23)") (class "Default")
      (node (ref "U$1") (pin "23") (pinfunction "P20_23") (pintype "bidirectional"))
    )
    (net (code "112") (name "unconnected-(U$1B-P21-Pad24)") (class "Default")
      (node (ref "U$1") (pin "24") (pinfunction "P21_24") (pintype "bidirectional"))
    )
    (net (code "113") (name "unconnected-(U$1B-P22-Pad25)") (class "Default")
      (node (ref "U$1") (pin "25") (pinfunction "P22_25") (pintype "bidirectional"))
    )
    (net (code "114") (name "unconnected-(U$1B-P23-Pad26)") (class "Default")
      (node (ref "U$1") (pin "26") (pinfunction "P23_26") (pintype "bidirectional"))
    )
    (net (code "115") (name "unconnected-(U$1B-P24-Pad31)") (class "Default")
      (node (ref "U$1") (pin "31") (pinfunction "P24_31") (pintype "bidirectional"))
    )
    (net (code "116") (name "unconnected-(U$1B-P25-Pad32)") (class "Default")
      (node (ref "U$1") (pin "32") (pinfunction "P25_32") (pintype "bidirectional"))
    )
    (net (code "117") (name "unconnected-(U$1B-P26-Pad33)") (class "Default")
      (node (ref "U$1") (pin "33") (pinfunction "P26_33") (pintype "bidirectional"))
    )
    (net (code "118") (name "unconnected-(U$1B-P27-Pad34)") (class "Default")
      (node (ref "U$1") (pin "34") (pinfunction "P27_34") (pintype "bidirectional"))
    )
    (net (code "119") (name "unconnected-(U$2-OE-Pad10)") (class "Default")
      (node (ref "U$2") (pin "10") (pinfunction "OE_10") (pintype "bidirectional"))
    )
    (net (code "120") (name "unconnected-(U$3-OE-Pad10)") (class "Default")
      (node (ref "U$3") (pin "10") (pinfunction "OE_10") (pintype "bidirectional"))
    )
    (net (code "121") (name "unconnected-(X1-AGND-PadP$14)") (class "Default")
      (node (ref "X1") (pin "P$14") (pinfunction "AGND_P$14") (pintype "bidirectional"))
    )
    (net (code "122") (name "unconnected-(X1-DGND-PadP$9)") (class "Default")
      (node (ref "X1") (pin "P$9") (pinfunction "DGND_P$9") (pintype "bidirectional"))
    )
    (net (code "123") (name "unconnected-(X1-VDD-PadP$16)") (class "Default")
      (node (ref "X1") (pin "P$16") (pinfunction "VDD_P$16") (pintype "bidirectional"))
    )
    (net (code "124") (name "unconnected-(X1-VREF-PadP$15)") (class "Default")
      (node (ref "X1") (pin "P$15") (pinfunction "VREF_P$15") (pintype "bidirectional"))
    )
    (net (code "125") (name "unconnected-(X2-AGND-PadP$14)") (class "Default")
      (node (ref "X2") (pin "P$14") (pinfunction "AGND_P$14") (pintype "bidirectional"))
    )
    (net (code "126") (name "unconnected-(X2-DGND-PadP$9)") (class "Default")
      (node (ref "X2") (pin "P$9") (pinfunction "DGND_P$9") (pintype "bidirectional"))
    )
    (net (code "127") (name "unconnected-(X2-VDD-PadP$16)") (class "Default")
      (node (ref "X2") (pin "P$16") (pinfunction "VDD_P$16") (pintype "bidirectional"))
    )
    (net (code "128") (name "unconnected-(X2-VREF-PadP$15)") (class "Default")
      (node (ref "X2") (pin "P$15") (pinfunction "VREF_P$15") (pintype "bidirectional"))
    )
    (net (code "129") (name "unconnected-(X3-AGND-PadP$14)") (class "Default")
      (node (ref "X3") (pin "P$14") (pinfunction "AGND_P$14") (pintype "bidirectional"))
    )
    (net (code "130") (name "unconnected-(X3-CH0-PadP$1)") (class "Default")
      (node (ref "X3") (pin "P$1") (pinfunction "CH0_P$1") (pintype "bidirectional"))
    )
    (net (code "131") (name "unconnected-(X3-CH1-PadP$2)") (class "Default")
      (node (ref "X3") (pin "P$2") (pinfunction "CH1_P$2") (pintype "bidirectional"))
    )
    (net (code "132") (name "unconnected-(X3-CH2-PadP$3)") (class "Default")
      (node (ref "X3") (pin "P$3") (pinfunction "CH2_P$3") (pintype "bidirectional"))
    )
    (net (code "133") (name "unconnected-(X3-CH3-PadP$4)") (class "Default")
      (node (ref "X3") (pin "P$4") (pinfunction "CH3_P$4") (pintype "bidirectional"))
    )
    (net (code "134") (name "unconnected-(X3-CH4-PadP$5)") (class "Default")
      (node (ref "X3") (pin "P$5") (pinfunction "CH4_P$5") (pintype "bidirectional"))
    )
    (net (code "135") (name "unconnected-(X3-CH5-PadP$6)") (class "Default")
      (node (ref "X3") (pin "P$6") (pinfunction "CH5_P$6") (pintype "bidirectional"))
    )
    (net (code "136") (name "unconnected-(X3-CH6-PadP$7)") (class "Default")
      (node (ref "X3") (pin "P$7") (pinfunction "CH6_P$7") (pintype "bidirectional"))
    )
    (net (code "137") (name "unconnected-(X3-CH7-PadP$8)") (class "Default")
      (node (ref "X3") (pin "P$8") (pinfunction "CH7_P$8") (pintype "bidirectional"))
    )
    (net (code "138") (name "unconnected-(X3-DGND-PadP$9)") (class "Default")
      (node (ref "X3") (pin "P$9") (pinfunction "DGND_P$9") (pintype "bidirectional"))
    )
    (net (code "139") (name "unconnected-(X3-VDD-PadP$16)") (class "Default")
      (node (ref "X3") (pin "P$16") (pinfunction "VDD_P$16") (pintype "bidirectional"))
    )
    (net (code "140") (name "unconnected-(X3-VREF-PadP$15)") (class "Default")
      (node (ref "X3") (pin "P$15") (pinfunction "VREF_P$15") (pintype "bidirectional"))
    )
  )
)
